# ProPrj_Flipper_-_TweenWave_2025-10-01.net
KiCad netlist of a schematic drawn in EasyEDA Pro
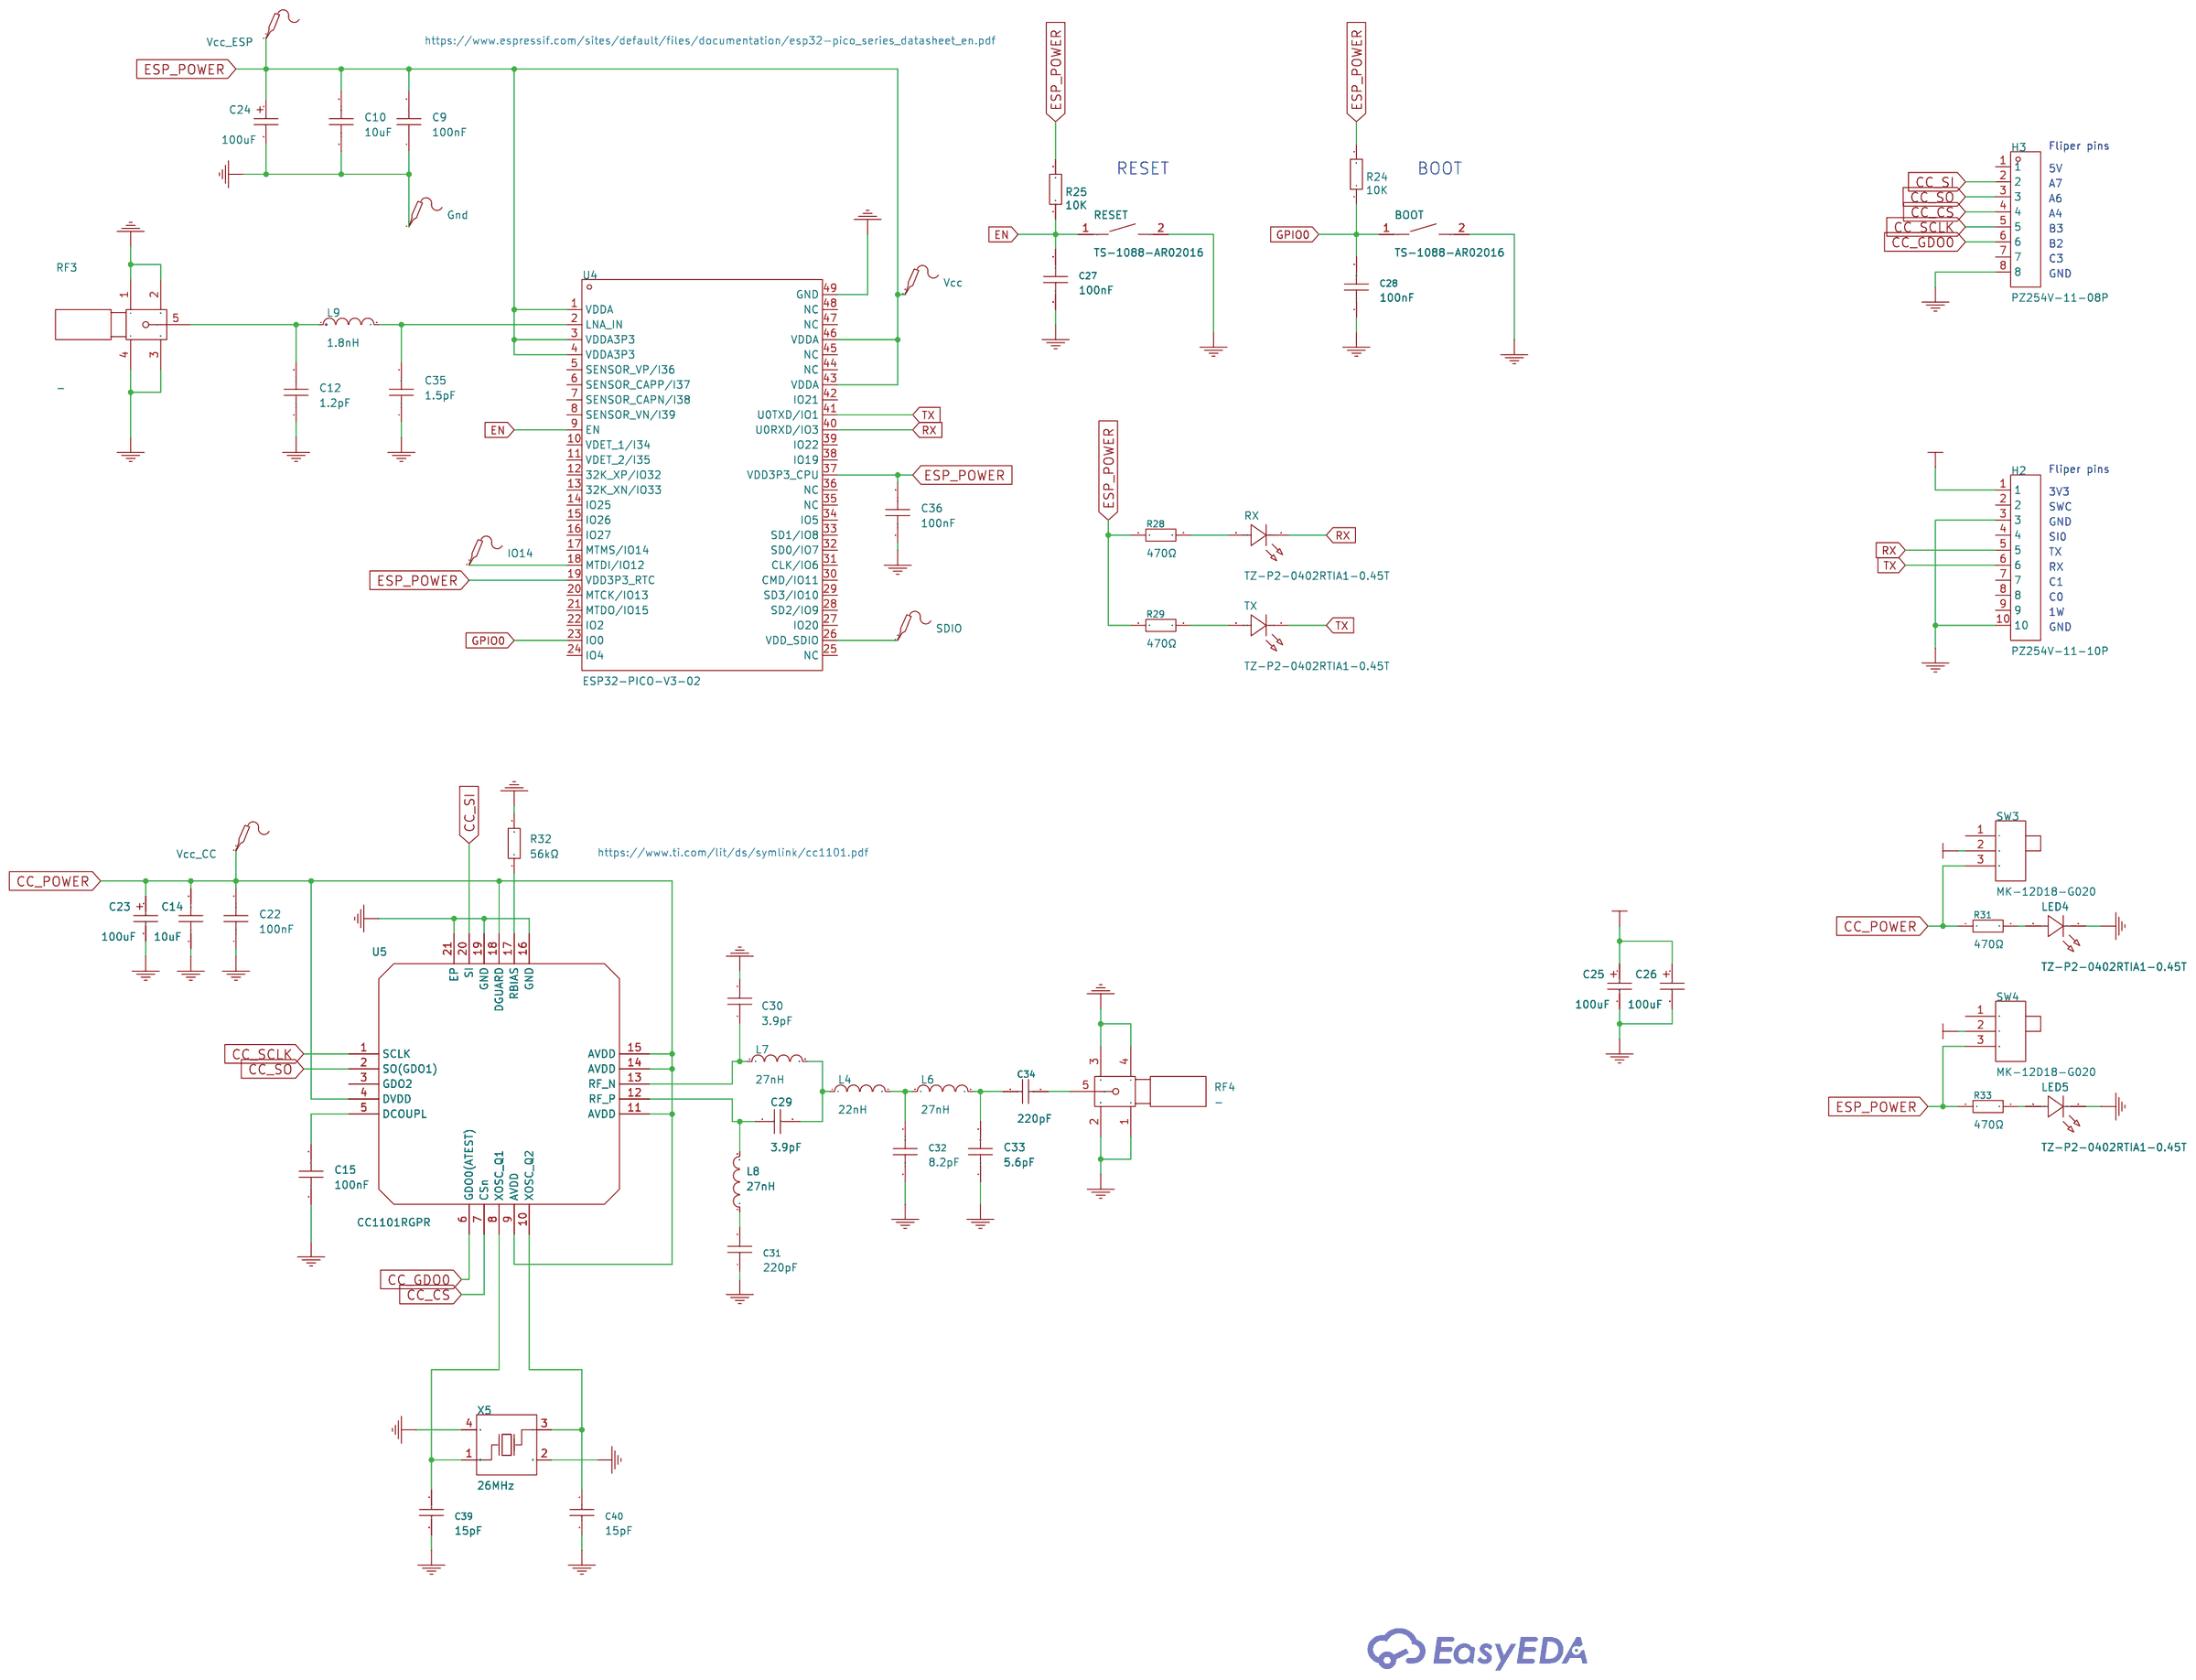
[diagram p0: schematic sheet]

(export (version "E")
  (design (tool "Eeschema 10.0.6"))
  (components
    (comp (ref "BOOT")
      (value "TS-1088-AR02016")
      (footprint "easyedapro:SW-SMD_L3.9-W3.0-P4.45")
      (fields (field (name "Manufacturer") "XUNPU(讯普)"))
      (libsource (lib "easyedapro") (part "TS-1088-AR02016"))
    )
    (comp (ref "C9")
      (value "100nF")
      (footprint "easyedapro:C0603")
      (description "Capacitance:100nF Tolerance:±10% Tolerance:±10% Voltage Rating:50V Temperature Coefficient:X7R")
      (fields
        (field (name "Manufacturer Part") "CC0603KRX7R9BB104")
        (field (name "Manufacturer") "YAGEO(国巨)")
      )
      (libsource (lib "easyedapro") (part "CC0603KRX7R9BB104"))
    )
    (comp (ref "C10")
      (value "10uF")
      (footprint "easyedapro:C0603")
      (fields
        (field (name "Manufacturer Part") "CL10A106MP8NNNC")
        (field (name "Manufacturer") "SAMSUNG(三星)")
      )
      (libsource (lib "easyedapro") (part "CL10A106MP8NNNC"))
    )
    (comp (ref "C12")
      (value "1.2pF")
      (footprint "easyedapro:C0201")
      (fields
        (field (name "Manufacturer Part") "GRM0335C1H1R2BA01D")
        (field (name "Manufacturer") "muRata(村田)")
      )
      (libsource (lib "easyedapro") (part "GRM0335C1H1R2BA01D"))
    )
    (comp (ref "C14")
      (value "10uF")
      (footprint "easyedapro:C0603")
      (fields
        (field (name "Manufacturer Part") "CL10A106MP8NNNC")
        (field (name "Manufacturer") "SAMSUNG(三星)")
      )
      (libsource (lib "easyedapro") (part "CL10A106MP8NNNC"))
    )
    (comp (ref "C15")
      (value "100nF")
      (footprint "easyedapro:C0603")
      (description "Capacitance:100nF Tolerance:±10% Tolerance:±10% Voltage Rating:50V Temperature Coefficient:X7R")
      (fields
        (field (name "Manufacturer Part") "CC0603KRX7R9BB104")
        (field (name "Manufacturer") "YAGEO(国巨)")
      )
      (libsource (lib "easyedapro") (part "CC0603KRX7R9BB104"))
    )
    (comp (ref "C22")
      (value "100nF")
      (footprint "easyedapro:C0603")
      (description "Capacitance:100nF Tolerance:±10% Tolerance:±10% Voltage Rating:50V Temperature Coefficient:X7R")
      (fields
        (field (name "Manufacturer Part") "CC0603KRX7R9BB104")
        (field (name "Manufacturer") "YAGEO(国巨)")
      )
      (libsource (lib "easyedapro") (part "CC0603KRX7R9BB104"))
    )
    (comp (ref "C23")
      (value "100uF")
      (footprint "easyedapro:CASE-B_3528")
      (fields (field (name "Manufacturer Part") "TAJB107K006RNJ") (field (name "Manufacturer") "Kyocera AVX"))
      (libsource (lib "easyedapro") (part "TAJB107K006RNJ"))
    )
    (comp (ref "C24")
      (value "100uF")
      (footprint "easyedapro:CASE-B_3528")
      (fields (field (name "Manufacturer Part") "TAJB107K006RNJ") (field (name "Manufacturer") "Kyocera AVX"))
      (libsource (lib "easyedapro") (part "TAJB107K006RNJ"))
    )
    (comp (ref "C25")
      (value "100uF")
      (footprint "easyedapro:CASE-B_3528")
      (fields (field (name "Manufacturer Part") "TAJB107K006RNJ") (field (name "Manufacturer") "Kyocera AVX"))
      (libsource (lib "easyedapro") (part "TAJB107K006RNJ"))
    )
    (comp (ref "C26")
      (value "100uF")
      (footprint "easyedapro:CASE-B_3528")
      (fields (field (name "Manufacturer Part") "TAJB107K006RNJ") (field (name "Manufacturer") "Kyocera AVX"))
      (libsource (lib "easyedapro") (part "TAJB107K006RNJ"))
    )
    (comp (ref "C27")
      (value "100nF")
      (footprint "easyedapro:C0402")
      (fields
        (field (name "Manufacturer Part") "CC0402KRX7R7BB104")
        (field (name "Manufacturer") "YAGEO(国巨)")
      )
      (libsource (lib "easyedapro") (part "CC0402KRX7R7BB104"))
    )
    (comp (ref "C28")
      (value "100nF")
      (footprint "easyedapro:C0402")
      (fields
        (field (name "Manufacturer Part") "CC0402KRX7R7BB104")
        (field (name "Manufacturer") "YAGEO(国巨)")
      )
      (libsource (lib "easyedapro") (part "CC0402KRX7R7BB104"))
    )
    (comp (ref "C29")
      (value "3.9pF")
      (footprint "easyedapro:C0402")
      (fields (field (name "Manufacturer Part") "0402CG3R9C500NT") (field (name "Manufacturer") "FH(风华)"))
      (libsource (lib "easyedapro") (part "0402CG3R9C500NT"))
    )
    (comp (ref "C30")
      (value "3.9pF")
      (footprint "easyedapro:C0402")
      (fields (field (name "Manufacturer Part") "0402CG3R9C500NT") (field (name "Manufacturer") "FH(风华)"))
      (libsource (lib "easyedapro") (part "0402CG3R9C500NT"))
    )
    (comp (ref "C31")
      (value "220pF")
      (footprint "easyedapro:C0402")
      (description "Capacitance:220pF Tolerance:±5% Tolerance:±5% Voltage Rating:50V Temperature Coefficient:NP0")
      (fields
        (field (name "Manufacturer Part") "CC0402JRNPO9BN221")
        (field (name "Manufacturer") "YAGEO(国巨)")
      )
      (libsource (lib "easyedapro") (part "CC0402JRNPO9BN221"))
    )
    (comp (ref "C32")
      (value "8.2pF")
      (footprint "easyedapro:C0402")
      (fields
        (field (name "Manufacturer Part") "CC0402BRNPO9BN8R2")
        (field (name "Manufacturer") "YAGEO(国巨)")
      )
      (libsource (lib "easyedapro") (part "CC0402BRNPO9BN8R2"))
    )
    (comp (ref "C33")
      (value "5.6pF")
      (footprint "easyedapro:C0402")
      (fields
        (field (name "Manufacturer Part") "CC0402BRNPO9BN5R6")
        (field (name "Manufacturer") "YAGEO(国巨)")
      )
      (libsource (lib "easyedapro") (part "CC0402BRNPO9BN5R6"))
    )
    (comp (ref "C34")
      (value "220pF")
      (footprint "easyedapro:C0402")
      (description "Capacitance:220pF Tolerance:±5% Tolerance:±5% Voltage Rating:50V Temperature Coefficient:NP0")
      (fields
        (field (name "Manufacturer Part") "CC0402JRNPO9BN221")
        (field (name "Manufacturer") "YAGEO(国巨)")
      )
      (libsource (lib "easyedapro") (part "CC0402JRNPO9BN221"))
    )
    (comp (ref "C35")
      (value "1.5pF")
      (footprint "easyedapro:C0201")
      (fields
        (field (name "Manufacturer Part") "GRM0335C1H1R5BA01D")
        (field (name "Manufacturer") "muRata(村田)")
      )
      (libsource (lib "easyedapro") (part "GRM0335C1H1R5BA01D"))
    )
    (comp (ref "C36")
      (value "100nF")
      (footprint "easyedapro:C0603")
      (description "Capacitance:100nF Tolerance:±10% Tolerance:±10% Voltage Rating:50V Temperature Coefficient:X7R")
      (fields
        (field (name "Manufacturer Part") "CC0603KRX7R9BB104")
        (field (name "Manufacturer") "YAGEO(国巨)")
      )
      (libsource (lib "easyedapro") (part "CC0603KRX7R9BB104"))
    )
    (comp (ref "C39")
      (value "15pF")
      (footprint "easyedapro:C0402")
      (fields
        (field (name "Manufacturer Part") "CC0402JRNPO9BN150")
        (field (name "Manufacturer") "YAGEO(国巨)")
      )
      (libsource (lib "easyedapro") (part "CC0402JRNPO9BN150"))
    )
    (comp (ref "C40")
      (value "15pF")
      (footprint "easyedapro:C0402")
      (fields
        (field (name "Manufacturer Part") "CC0402JRNPO9BN150")
        (field (name "Manufacturer") "YAGEO(国巨)")
      )
      (libsource (lib "easyedapro") (part "CC0402JRNPO9BN150"))
    )
    (comp (ref "Gnd")
      (value "~")
      (footprint "easyedapro:Test-Point-0.5mm")
      (description "Test Point 测试点")
      (libsource (lib "easyedapro") (part "Test-Point"))
    )
    (comp (ref "H2")
      (value "PZ254V-11-10P")
      (footprint "easyedapro:HDR-TH_10P-P2.54-V-M")
      (fields (field (name "Manufacturer") "XFCN(兴飞)"))
      (libsource (lib "easyedapro") (part "PZ254V-11-10P"))
    )
    (comp (ref "H3")
      (value "PZ254V-11-08P")
      (footprint "easyedapro:HDR-TH_8P-P2.54-V-M")
      (fields (field (name "Manufacturer") "XFCN(兴飞)"))
      (libsource (lib "easyedapro") (part "PZ254V-11-08P"))
    )
    (comp (ref "IO14")
      (value "~")
      (footprint "easyedapro:Test-Point-0.5mm")
      (description "Test Point 测试点")
      (libsource (lib "easyedapro") (part "Test-Point"))
    )
    (comp (ref "L4")
      (value "22nH")
      (footprint "easyedapro:L0402")
      (fields (field (name "Manufacturer Part") "LQG15HS22NJ02D") (field (name "Manufacturer") "muRata(村田)"))
      (libsource (lib "easyedapro") (part "LQG15HS22NJ02D"))
    )
    (comp (ref "L6")
      (value "27nH")
      (footprint "easyedapro:L0402-RD")
      (fields (field (name "Manufacturer Part") "LQG15HS27NJ02D") (field (name "Manufacturer") "muRata(村田)"))
      (libsource (lib "easyedapro") (part "LQG15HS27NJ02D"))
    )
    (comp (ref "L7")
      (value "27nH")
      (footprint "easyedapro:L0402-RD")
      (fields (field (name "Manufacturer Part") "LQG15HS27NJ02D") (field (name "Manufacturer") "muRata(村田)"))
      (libsource (lib "easyedapro") (part "LQG15HS27NJ02D"))
    )
    (comp (ref "L8")
      (value "27nH")
      (footprint "easyedapro:L0402-RD")
      (fields (field (name "Manufacturer Part") "LQG15HS27NJ02D") (field (name "Manufacturer") "muRata(村田)"))
      (libsource (lib "easyedapro") (part "LQG15HS27NJ02D"))
    )
    (comp (ref "L9")
      (value "1.8nH")
      (footprint "easyedapro:L0201-RD")
      (fields (field (name "Manufacturer Part") "LQP03TN1N8B02D") (field (name "Manufacturer") "muRata(村田)"))
      (libsource (lib "easyedapro") (part "LQP03TN1N8B02D"))
    )
    (comp (ref "LED4")
      (value "TZ-P2-0402RTIA1-0.45T")
      (footprint "easyedapro:LED0402-RD_RED")
      (fields (field (name "Manufacturer") "TUOZHAN(拓展光电)"))
      (libsource (lib "easyedapro") (part "TZ-P2-0402RTIA1-0.45T"))
    )
    (comp (ref "LED5")
      (value "TZ-P2-0402RTIA1-0.45T")
      (footprint "easyedapro:LED0402-RD_RED")
      (fields (field (name "Manufacturer") "TUOZHAN(拓展光电)"))
      (libsource (lib "easyedapro") (part "TZ-P2-0402RTIA1-0.45T"))
    )
    (comp (ref "R24")
      (value "10K")
      (footprint "easyedapro:R0603")
      (fields (field (name "Manufacturer Part") "RC0603DR-0710KL") (field (name "Manufacturer") "YAGEO(国巨)"))
      (libsource (lib "easyedapro") (part "10K"))
    )
    (comp (ref "R25")
      (value "10K")
      (footprint "easyedapro:R0603")
      (fields (field (name "Manufacturer Part") "RC0603DR-0710KL") (field (name "Manufacturer") "YAGEO(国巨)"))
      (libsource (lib "easyedapro") (part "10K"))
    )
    (comp (ref "R28")
      (value "470Ω")
      (footprint "easyedapro:R0402")
      (fields
        (field (name "Manufacturer Part") "0402WGF4700TCE")
        (field (name "Manufacturer") "UNI-ROYAL(厚声)")
      )
      (libsource (lib "easyedapro") (part "0402WGF4700TCE"))
    )
    (comp (ref "R29")
      (value "470Ω")
      (footprint "easyedapro:R0402")
      (fields
        (field (name "Manufacturer Part") "0402WGF4700TCE")
        (field (name "Manufacturer") "UNI-ROYAL(厚声)")
      )
      (libsource (lib "easyedapro") (part "0402WGF4700TCE"))
    )
    (comp (ref "R31")
      (value "470Ω")
      (footprint "easyedapro:R0402")
      (fields
        (field (name "Manufacturer Part") "0402WGF4700TCE")
        (field (name "Manufacturer") "UNI-ROYAL(厚声)")
      )
      (libsource (lib "easyedapro") (part "0402WGF4700TCE"))
    )
    (comp (ref "R32")
      (value "56kΩ")
      (footprint "easyedapro:R0402")
      (fields
        (field (name "Manufacturer Part") "0402WGF5602TCE")
        (field (name "Manufacturer") "UNI-ROYAL(厚声)")
      )
      (libsource (lib "easyedapro") (part "0402WGF5602TCE"))
    )
    (comp (ref "R33")
      (value "470Ω")
      (footprint "easyedapro:R0402")
      (fields
        (field (name "Manufacturer Part") "0402WGF4700TCE")
        (field (name "Manufacturer") "UNI-ROYAL(厚声)")
      )
      (libsource (lib "easyedapro") (part "0402WGF4700TCE"))
    )
    (comp (ref "RESET")
      (value "TS-1088-AR02016")
      (footprint "easyedapro:SW-SMD_L3.9-W3.0-P4.45")
      (fields (field (name "Manufacturer") "XUNPU(讯普)"))
      (libsource (lib "easyedapro") (part "TS-1088-AR02016"))
    )
    (comp (ref "RF3")
      (value "-")
      (footprint "easyedapro:SMA-SMD_BWSMA-KE-P001")
      (fields
        (field (name "Manufacturer Part") "BWSMA-KE-P001")
        (field (name "Manufacturer") "BAT WIRELESS(蝙蝠无线)")
      )
      (libsource (lib "easyedapro") (part "BWSMA-KE-P001"))
    )
    (comp (ref "RF4")
      (value "-")
      (footprint "easyedapro:SMA-SMD_BWSMA-KE-P001")
      (fields
        (field (name "Manufacturer Part") "BWSMA-KE-P001")
        (field (name "Manufacturer") "BAT WIRELESS(蝙蝠无线)")
      )
      (libsource (lib "easyedapro") (part "BWSMA-KE-P001"))
    )
    (comp (ref "RX")
      (value "TZ-P2-0402RTIA1-0.45T")
      (footprint "easyedapro:LED0402-RD_RED")
      (fields (field (name "Manufacturer") "TUOZHAN(拓展光电)"))
      (libsource (lib "easyedapro") (part "TZ-P2-0402RTIA1-0.45T"))
    )
    (comp (ref "SDIO")
      (value "~")
      (footprint "easyedapro:Test-Point-0.5mm")
      (description "Test Point 测试点")
      (libsource (lib "easyedapro") (part "Test-Point"))
    )
    (comp (ref "SW3")
      (value "MK-12D18-G020")
      (footprint "easyedapro:SW-TH_MK-12D18-G040")
      (fields (field (name "Manufacturer") "G-Switch(品赞)"))
      (libsource (lib "easyedapro") (part "MK-12D18-G020"))
    )
    (comp (ref "SW4")
      (value "MK-12D18-G020")
      (footprint "easyedapro:SW-TH_MK-12D18-G040")
      (fields (field (name "Manufacturer") "G-Switch(品赞)"))
      (libsource (lib "easyedapro") (part "MK-12D18-G020"))
    )
    (comp (ref "TX")
      (value "TZ-P2-0402RTIA1-0.45T")
      (footprint "easyedapro:LED0402-RD_RED")
      (fields (field (name "Manufacturer") "TUOZHAN(拓展光电)"))
      (libsource (lib "easyedapro") (part "TZ-P2-0402RTIA1-0.45T"))
    )
    (comp (ref "U4")
      (value "ESP32-PICO-V3-02")
      (footprint "easyedapro:QFN-48_L7.0-W7.0-P0.50-BL-EP5.1")
      (fields (field (name "Manufacturer") "ESPRESSIF(乐鑫)"))
      (libsource (lib "easyedapro") (part "ESP32-PICO-V3-02"))
    )
    (comp (ref "U5")
      (value "CC1101RGPR")
      (footprint "easyedapro:QFN-20_L4.0-W4.0-P0.5-TL-EP")
      (fields (field (name "Manufacturer") "TI(德州仪器)"))
      (libsource (lib "easyedapro") (part "CC1101RGPR"))
    )
    (comp (ref "Vcc")
      (value "~")
      (footprint "easyedapro:Test-Point-0.5mm")
      (description "Test Point 测试点")
      (libsource (lib "easyedapro") (part "Test-Point"))
    )
    (comp (ref "Vcc_CC")
      (value "~")
      (footprint "easyedapro:Test-Point-0.5mm")
      (description "Test Point 测试点")
      (libsource (lib "easyedapro") (part "Test-Point"))
    )
    (comp (ref "Vcc_ESP")
      (value "~")
      (footprint "easyedapro:Test-Point-0.5mm")
      (description "Test Point 测试点")
      (libsource (lib "easyedapro") (part "Test-Point"))
    )
    (comp (ref "X5")
      (value "26MHz")
      (footprint "easyedapro:CRYSTAL-SMD_4P-L3.2-W2.5-BL")
      (fields (field (name "Manufacturer Part") "X322526MMB4SI") (field (name "Manufacturer") "YXC(扬兴晶振)"))
      (libsource (lib "easyedapro") (part "X322526MMB4SI"))
    )
  )
  (nets
    (net (code "1") (name "3V3") (class "Default")
      (node (ref "C25") (pin "1") (pinfunction "1_1") (pintype "input"))
      (node (ref "C26") (pin "1") (pinfunction "1_1") (pintype "input"))
      (node (ref "H2") (pin "1") (pinfunction "1_1") (pintype "unspecified"))
      (node (ref "SW3") (pin "2") (pinfunction "2_2") (pintype "unspecified"))
      (node (ref "SW4") (pin "2") (pinfunction "2_2") (pintype "unspecified"))
    )
    (net (code "2") (name "CC_CS") (class "Default")
      (node (ref "H3") (pin "4") (pinfunction "4_4") (pintype "unspecified"))
      (node (ref "U5") (pin "7") (pinfunction "CSn_7") (pintype "unspecified"))
    )
    (net (code "3") (name "CC_GDO0") (class "Default")
      (node (ref "H3") (pin "6") (pinfunction "6_6") (pintype "unspecified"))
      (node (ref "U5") (pin "6") (pinfunction "GDO0(ATEST)_6") (pintype "unspecified"))
    )
    (net (code "4") (name "CC_POWER") (class "Default")
      (node (ref "C14") (pin "2") (pinfunction "2_2") (pintype "unspecified"))
      (node (ref "C22") (pin "2") (pinfunction "2_2") (pintype "unspecified"))
      (node (ref "C23") (pin "1") (pinfunction "1_1") (pintype "input"))
      (node (ref "R31") (pin "1") (pinfunction "1_1") (pintype "input"))
      (node (ref "SW3") (pin "3") (pinfunction "3_3") (pintype "unspecified"))
      (node (ref "U5") (pin "11") (pinfunction "AVDD_11") (pintype "unspecified"))
      (node (ref "U5") (pin "14") (pinfunction "AVDD_14") (pintype "unspecified"))
      (node (ref "U5") (pin "15") (pinfunction "AVDD_15") (pintype "unspecified"))
      (node (ref "U5") (pin "18") (pinfunction "DGUARD_18") (pintype "unspecified"))
      (node (ref "U5") (pin "4") (pinfunction "DVDD_4") (pintype "unspecified"))
      (node (ref "U5") (pin "9") (pinfunction "AVDD_9") (pintype "unspecified"))
      (node (ref "Vcc_CC") (pin "1") (pinfunction "1_1") (pintype "unspecified"))
    )
    (net (code "5") (name "CC_SCLK") (class "Default")
      (node (ref "H3") (pin "5") (pinfunction "5_5") (pintype "unspecified"))
      (node (ref "U5") (pin "1") (pinfunction "SCLK_1") (pintype "unspecified"))
    )
    (net (code "6") (name "CC_SI") (class "Default")
      (node (ref "H3") (pin "2") (pinfunction "2_2") (pintype "unspecified"))
      (node (ref "U5") (pin "20") (pinfunction "SI_20") (pintype "unspecified"))
    )
    (net (code "7") (name "CC_SO") (class "Default")
      (node (ref "H3") (pin "3") (pinfunction "3_3") (pintype "unspecified"))
      (node (ref "U5") (pin "2") (pinfunction "SO(GDO1)_2") (pintype "unspecified"))
    )
    (net (code "8") (name "EN") (class "Default")
      (node (ref "C27") (pin "2") (pinfunction "2_2") (pintype "input"))
      (node (ref "R25") (pin "1") (pinfunction "1_1") (pintype "input"))
      (node (ref "RESET") (pin "1") (pinfunction "1_1") (pintype "unspecified"))
      (node (ref "U4") (pin "9") (pinfunction "EN_9") (pintype "unspecified"))
    )
    (net (code "9") (name "ESP_POWER") (class "Default")
      (node (ref "C10") (pin "2") (pinfunction "2_2") (pintype "unspecified"))
      (node (ref "C24") (pin "1") (pinfunction "1_1") (pintype "input"))
      (node (ref "C36") (pin "2") (pinfunction "2_2") (pintype "unspecified"))
      (node (ref "C9") (pin "2") (pinfunction "2_2") (pintype "unspecified"))
      (node (ref "R24") (pin "2") (pinfunction "2_2") (pintype "input"))
      (node (ref "R25") (pin "2") (pinfunction "2_2") (pintype "input"))
      (node (ref "R28") (pin "1") (pinfunction "1_1") (pintype "input"))
      (node (ref "R29") (pin "1") (pinfunction "1_1") (pintype "input"))
      (node (ref "R33") (pin "1") (pinfunction "1_1") (pintype "input"))
      (node (ref "SW4") (pin "3") (pinfunction "3_3") (pintype "unspecified"))
      (node (ref "U4") (pin "1") (pinfunction "VDDA_1") (pintype "unspecified"))
      (node (ref "U4") (pin "19") (pinfunction "VDD3P3_RTC_19") (pintype "unspecified"))
      (node (ref "U4") (pin "3") (pinfunction "VDDA3P3_3") (pintype "unspecified"))
      (node (ref "U4") (pin "37") (pinfunction "VDD3P3_CPU_37") (pintype "unspecified"))
      (node (ref "U4") (pin "4") (pinfunction "VDDA3P3_4") (pintype "unspecified"))
      (node (ref "U4") (pin "43") (pinfunction "VDDA_43") (pintype "unspecified"))
      (node (ref "U4") (pin "46") (pinfunction "VDDA_46") (pintype "unspecified"))
      (node (ref "Vcc") (pin "1") (pinfunction "1_1") (pintype "unspecified"))
      (node (ref "Vcc_ESP") (pin "1") (pinfunction "1_1") (pintype "unspecified"))
    )
    (net (code "10") (name "GND") (class "Default")
      (node (ref "BOOT") (pin "2") (pinfunction "2_2") (pintype "unspecified"))
      (node (ref "C10") (pin "1") (pinfunction "1_1") (pintype "unspecified"))
      (node (ref "C12") (pin "1") (pinfunction "1_1") (pintype "unspecified"))
      (node (ref "C14") (pin "1") (pinfunction "1_1") (pintype "unspecified"))
      (node (ref "C15") (pin "1") (pinfunction "1_1") (pintype "unspecified"))
      (node (ref "C22") (pin "1") (pinfunction "1_1") (pintype "unspecified"))
      (node (ref "C23") (pin "2") (pinfunction "2_2") (pintype "input"))
      (node (ref "C24") (pin "2") (pinfunction "2_2") (pintype "input"))
      (node (ref "C25") (pin "2") (pinfunction "2_2") (pintype "input"))
      (node (ref "C26") (pin "2") (pinfunction "2_2") (pintype "input"))
      (node (ref "C27") (pin "1") (pinfunction "1_1") (pintype "input"))
      (node (ref "C28") (pin "1") (pinfunction "1_1") (pintype "input"))
      (node (ref "C30") (pin "2") (pinfunction "2_2") (pintype "input"))
      (node (ref "C31") (pin "1") (pinfunction "1_1") (pintype "input"))
      (node (ref "C32") (pin "2") (pinfunction "2_2") (pintype "input"))
      (node (ref "C33") (pin "1") (pinfunction "1_1") (pintype "unspecified"))
      (node (ref "C35") (pin "1") (pinfunction "1_1") (pintype "unspecified"))
      (node (ref "C36") (pin "1") (pinfunction "1_1") (pintype "unspecified"))
      (node (ref "C39") (pin "1") (pinfunction "1_1") (pintype "input"))
      (node (ref "C40") (pin "1") (pinfunction "1_1") (pintype "input"))
      (node (ref "C9") (pin "1") (pinfunction "1_1") (pintype "unspecified"))
      (node (ref "Gnd") (pin "1") (pinfunction "1_1") (pintype "unspecified"))
      (node (ref "H2") (pin "10") (pinfunction "10_10") (pintype "unspecified"))
      (node (ref "H2") (pin "3") (pinfunction "3_3") (pintype "unspecified"))
      (node (ref "H3") (pin "8") (pinfunction "8_8") (pintype "unspecified"))
      (node (ref "LED4") (pin "1") (pinfunction "K_1") (pintype "unspecified"))
      (node (ref "LED5") (pin "1") (pinfunction "K_1") (pintype "unspecified"))
      (node (ref "R32") (pin "2") (pinfunction "2_2") (pintype "input"))
      (node (ref "RESET") (pin "2") (pinfunction "2_2") (pintype "unspecified"))
      (node (ref "RF3") (pin "1") (pinfunction "1_1") (pintype "unspecified"))
      (node (ref "RF3") (pin "2") (pinfunction "2_2") (pintype "unspecified"))
      (node (ref "RF3") (pin "3") (pinfunction "3_3") (pintype "unspecified"))
      (node (ref "RF3") (pin "4") (pinfunction "4_4") (pintype "unspecified"))
      (node (ref "RF4") (pin "1") (pinfunction "1_1") (pintype "unspecified"))
      (node (ref "RF4") (pin "2") (pinfunction "2_2") (pintype "unspecified"))
      (node (ref "RF4") (pin "3") (pinfunction "3_3") (pintype "unspecified"))
      (node (ref "RF4") (pin "4") (pinfunction "4_4") (pintype "unspecified"))
      (node (ref "U4") (pin "49") (pinfunction "GND_49") (pintype "unspecified"))
      (node (ref "U5") (pin "16") (pinfunction "GND_16") (pintype "unspecified"))
      (node (ref "U5") (pin "19") (pinfunction "GND_19") (pintype "unspecified"))
      (node (ref "U5") (pin "21") (pinfunction "EP_21") (pintype "unspecified"))
      (node (ref "X5") (pin "2") (pinfunction "GND_2") (pintype "unspecified"))
      (node (ref "X5") (pin "4") (pinfunction "GND_4") (pintype "unspecified"))
    )
    (net (code "11") (name "GPIO0") (class "Default")
      (node (ref "BOOT") (pin "1") (pinfunction "1_1") (pintype "unspecified"))
      (node (ref "C28") (pin "2") (pinfunction "2_2") (pintype "input"))
      (node (ref "R24") (pin "1") (pinfunction "1_1") (pintype "input"))
      (node (ref "U4") (pin "23") (pinfunction "IO0_23") (pintype "unspecified"))
    )
    (net (code "12") (name "Net-(C12-Pad2)") (class "Default")
      (node (ref "C12") (pin "2") (pinfunction "2_2") (pintype "unspecified"))
      (node (ref "L9") (pin "1") (pinfunction "1_1") (pintype "input"))
      (node (ref "RF3") (pin "5") (pinfunction "5_5") (pintype "unspecified"))
    )
    (net (code "13") (name "Net-(C29-Pad2)") (class "Default")
      (node (ref "C29") (pin "2") (pinfunction "2_2") (pintype "input"))
      (node (ref "L4") (pin "1") (pinfunction "1_1") (pintype "unspecified"))
      (node (ref "L7") (pin "2") (pinfunction "2_2") (pintype "unspecified"))
    )
    (net (code "14") (name "Net-(C31-Pad2)") (class "Default")
      (node (ref "C31") (pin "2") (pinfunction "2_2") (pintype "input"))
      (node (ref "L8") (pin "1") (pinfunction "1_1") (pintype "unspecified"))
    )
    (net (code "15") (name "Net-(C32-Pad1)") (class "Default")
      (node (ref "C32") (pin "1") (pinfunction "1_1") (pintype "input"))
      (node (ref "L4") (pin "2") (pinfunction "2_2") (pintype "unspecified"))
      (node (ref "L6") (pin "1") (pinfunction "1_1") (pintype "unspecified"))
    )
    (net (code "16") (name "Net-(C33-Pad2)") (class "Default")
      (node (ref "C33") (pin "2") (pinfunction "2_2") (pintype "unspecified"))
      (node (ref "C34") (pin "2") (pinfunction "2_2") (pintype "input"))
      (node (ref "L6") (pin "2") (pinfunction "2_2") (pintype "unspecified"))
    )
    (net (code "17") (name "Net-(C34-Pad1)") (class "Default")
      (node (ref "C34") (pin "1") (pinfunction "1_1") (pintype "input"))
      (node (ref "RF4") (pin "5") (pinfunction "5_5") (pintype "unspecified"))
    )
    (net (code "18") (name "Net-(LED4-A)") (class "Default")
      (node (ref "LED4") (pin "2") (pinfunction "A_2") (pintype "unspecified"))
      (node (ref "R31") (pin "2") (pinfunction "2_2") (pintype "input"))
    )
    (net (code "19") (name "Net-(LED5-A)") (class "Default")
      (node (ref "LED5") (pin "2") (pinfunction "A_2") (pintype "unspecified"))
      (node (ref "R33") (pin "2") (pinfunction "2_2") (pintype "input"))
    )
    (net (code "20") (name "Net-(RX-A)") (class "Default")
      (node (ref "R28") (pin "2") (pinfunction "2_2") (pintype "input"))
      (node (ref "RX") (pin "2") (pinfunction "A_2") (pintype "unspecified"))
    )
    (net (code "21") (name "Net-(TX-A)") (class "Default")
      (node (ref "R29") (pin "2") (pinfunction "2_2") (pintype "input"))
      (node (ref "TX") (pin "2") (pinfunction "A_2") (pintype "unspecified"))
    )
    (net (code "22") (name "Net-(U4-LNA_IN)") (class "Default")
      (node (ref "C35") (pin "2") (pinfunction "2_2") (pintype "unspecified"))
      (node (ref "L9") (pin "2") (pinfunction "2_2") (pintype "input"))
      (node (ref "U4") (pin "2") (pinfunction "LNA_IN_2") (pintype "unspecified"))
    )
    (net (code "23") (name "Net-(U4-MTDI{slash}IO12)") (class "Default")
      (node (ref "IO14") (pin "1") (pinfunction "1_1") (pintype "unspecified"))
      (node (ref "U4") (pin "18") (pinfunction "MTDI/IO12_18") (pintype "unspecified"))
    )
    (net (code "24") (name "Net-(U4-VDD_SDIO)") (class "Default")
      (node (ref "SDIO") (pin "1") (pinfunction "1_1") (pintype "unspecified"))
      (node (ref "U4") (pin "26") (pinfunction "VDD_SDIO_26") (pintype "unspecified"))
    )
    (net (code "25") (name "Net-(U5-DCOUPL)") (class "Default")
      (node (ref "C15") (pin "2") (pinfunction "2_2") (pintype "unspecified"))
      (node (ref "U5") (pin "5") (pinfunction "DCOUPL_5") (pintype "unspecified"))
    )
    (net (code "26") (name "Net-(U5-RBIAS)") (class "Default")
      (node (ref "R32") (pin "1") (pinfunction "1_1") (pintype "input"))
      (node (ref "U5") (pin "17") (pinfunction "RBIAS_17") (pintype "unspecified"))
    )
    (net (code "27") (name "Net-(U5-RF_N)") (class "Default")
      (node (ref "C30") (pin "1") (pinfunction "1_1") (pintype "input"))
      (node (ref "L7") (pin "1") (pinfunction "1_1") (pintype "unspecified"))
      (node (ref "U5") (pin "13") (pinfunction "RF_N_13") (pintype "unspecified"))
    )
    (net (code "28") (name "Net-(U5-RF_P)") (class "Default")
      (node (ref "C29") (pin "1") (pinfunction "1_1") (pintype "input"))
      (node (ref "L8") (pin "2") (pinfunction "2_2") (pintype "unspecified"))
      (node (ref "U5") (pin "12") (pinfunction "RF_P_12") (pintype "unspecified"))
    )
    (net (code "29") (name "Net-(U5-XOSC_Q1)") (class "Default")
      (node (ref "C39") (pin "2") (pinfunction "2_2") (pintype "input"))
      (node (ref "U5") (pin "8") (pinfunction "XOSC_Q1_8") (pintype "unspecified"))
      (node (ref "X5") (pin "1") (pinfunction "OSC1_1") (pintype "unspecified"))
    )
    (net (code "30") (name "Net-(U5-XOSC_Q2)") (class "Default")
      (node (ref "C40") (pin "2") (pinfunction "2_2") (pintype "input"))
      (node (ref "U5") (pin "10") (pinfunction "XOSC_Q2_10") (pintype "unspecified"))
      (node (ref "X5") (pin "3") (pinfunction "OSC2_3") (pintype "unspecified"))
    )
    (net (code "31") (name "RX") (class "Default")
      (node (ref "H2") (pin "5") (pinfunction "5_5") (pintype "unspecified"))
      (node (ref "RX") (pin "1") (pinfunction "K_1") (pintype "unspecified"))
      (node (ref "U4") (pin "40") (pinfunction "U0RXD/IO3_40") (pintype "unspecified"))
    )
    (net (code "32") (name "TX") (class "Default")
      (node (ref "H2") (pin "6") (pinfunction "6_6") (pintype "unspecified"))
      (node (ref "TX") (pin "1") (pinfunction "K_1") (pintype "unspecified"))
      (node (ref "U4") (pin "41") (pinfunction "U0TXD/IO1_41") (pintype "unspecified"))
    )
    (net (code "33") (name "unconnected-(H2-Pad2)") (class "Default")
      (node (ref "H2") (pin "2") (pinfunction "2_2") (pintype "unspecified"))
    )
    (net (code "34") (name "unconnected-(H2-Pad4)") (class "Default")
      (node (ref "H2") (pin "4") (pinfunction "4_4") (pintype "unspecified"))
    )
    (net (code "35") (name "unconnected-(H2-Pad7)") (class "Default")
      (node (ref "H2") (pin "7") (pinfunction "7_7") (pintype "unspecified"))
    )
    (net (code "36") (name "unconnected-(H2-Pad8)") (class "Default")
      (node (ref "H2") (pin "8") (pinfunction "8_8") (pintype "unspecified"))
    )
    (net (code "37") (name "unconnected-(H2-Pad9)") (class "Default")
      (node (ref "H2") (pin "9") (pinfunction "9_9") (pintype "unspecified"))
    )
    (net (code "38") (name "unconnected-(H3-Pad1)") (class "Default")
      (node (ref "H3") (pin "1") (pinfunction "1_1") (pintype "unspecified"))
    )
    (net (code "39") (name "unconnected-(H3-Pad7)") (class "Default")
      (node (ref "H3") (pin "7") (pinfunction "7_7") (pintype "unspecified"))
    )
    (net (code "40") (name "unconnected-(SW3-Pad1)") (class "Default")
      (node (ref "SW3") (pin "1") (pinfunction "1_1") (pintype "unspecified"))
    )
    (net (code "41") (name "unconnected-(SW4-Pad1)") (class "Default")
      (node (ref "SW4") (pin "1") (pinfunction "1_1") (pintype "unspecified"))
    )
    (net (code "42") (name "unconnected-(U4-32K_XN{slash}IO33-Pad13)") (class "Default")
      (node (ref "U4") (pin "13") (pinfunction "32K_XN/IO33_13") (pintype "unspecified"))
    )
    (net (code "43") (name "unconnected-(U4-32K_XP{slash}IO32-Pad12)") (class "Default")
      (node (ref "U4") (pin "12") (pinfunction "32K_XP/IO32_12") (pintype "unspecified"))
    )
    (net (code "44") (name "unconnected-(U4-CLK{slash}IO6-Pad31)") (class "Default")
      (node (ref "U4") (pin "31") (pinfunction "CLK/IO6_31") (pintype "unspecified"))
    )
    (net (code "45") (name "unconnected-(U4-CMD{slash}IO11-Pad30)") (class "Default")
      (node (ref "U4") (pin "30") (pinfunction "CMD/IO11_30") (pintype "unspecified"))
    )
    (net (code "46") (name "unconnected-(U4-IO2-Pad22)") (class "Default")
      (node (ref "U4") (pin "22") (pinfunction "IO2_22") (pintype "unspecified"))
    )
    (net (code "47") (name "unconnected-(U4-IO4-Pad24)") (class "Default")
      (node (ref "U4") (pin "24") (pinfunction "IO4_24") (pintype "unspecified"))
    )
    (net (code "48") (name "unconnected-(U4-IO5-Pad34)") (class "Default")
      (node (ref "U4") (pin "34") (pinfunction "IO5_34") (pintype "unspecified"))
    )
    (net (code "49") (name "unconnected-(U4-IO19-Pad38)") (class "Default")
      (node (ref "U4") (pin "38") (pinfunction "IO19_38") (pintype "unspecified"))
    )
    (net (code "50") (name "unconnected-(U4-IO20-Pad27)") (class "Default")
      (node (ref "U4") (pin "27") (pinfunction "IO20_27") (pintype "unspecified"))
    )
    (net (code "51") (name "unconnected-(U4-IO21-Pad42)") (class "Default")
      (node (ref "U4") (pin "42") (pinfunction "IO21_42") (pintype "unspecified"))
    )
    (net (code "52") (name "unconnected-(U4-IO22-Pad39)") (class "Default")
      (node (ref "U4") (pin "39") (pinfunction "IO22_39") (pintype "unspecified"))
    )
    (net (code "53") (name "unconnected-(U4-IO25-Pad14)") (class "Default")
      (node (ref "U4") (pin "14") (pinfunction "IO25_14") (pintype "unspecified"))
    )
    (net (code "54") (name "unconnected-(U4-IO26-Pad15)") (class "Default")
      (node (ref "U4") (pin "15") (pinfunction "IO26_15") (pintype "unspecified"))
    )
    (net (code "55") (name "unconnected-(U4-IO27-Pad16)") (class "Default")
      (node (ref "U4") (pin "16") (pinfunction "IO27_16") (pintype "unspecified"))
    )
    (net (code "56") (name "unconnected-(U4-MTCK{slash}IO13-Pad20)") (class "Default")
      (node (ref "U4") (pin "20") (pinfunction "MTCK/IO13_20") (pintype "unspecified"))
    )
    (net (code "57") (name "unconnected-(U4-MTDO{slash}IO15-Pad21)") (class "Default")
      (node (ref "U4") (pin "21") (pinfunction "MTDO/IO15_21") (pintype "unspecified"))
    )
    (net (code "58") (name "unconnected-(U4-MTMS{slash}IO14-Pad17)") (class "Default")
      (node (ref "U4") (pin "17") (pinfunction "MTMS/IO14_17") (pintype "unspecified"))
    )
    (net (code "59") (name "unconnected-(U4-NC-Pad25)") (class "Default")
      (node (ref "U4") (pin "25") (pinfunction "NC_25") (pintype "unspecified"))
    )
    (net (code "60") (name "unconnected-(U4-NC-Pad35)") (class "Default")
      (node (ref "U4") (pin "35") (pinfunction "NC_35") (pintype "unspecified"))
    )
    (net (code "61") (name "unconnected-(U4-NC-Pad36)") (class "Default")
      (node (ref "U4") (pin "36") (pinfunction "NC_36") (pintype "unspecified"))
    )
    (net (code "62") (name "unconnected-(U4-NC-Pad44)") (class "Default")
      (node (ref "U4") (pin "44") (pinfunction "NC_44") (pintype "unspecified"))
    )
    (net (code "63") (name "unconnected-(U4-NC-Pad45)") (class "Default")
      (node (ref "U4") (pin "45") (pinfunction "NC_45") (pintype "unspecified"))
    )
    (net (code "64") (name "unconnected-(U4-NC-Pad47)") (class "Default")
      (node (ref "U4") (pin "47") (pinfunction "NC_47") (pintype "unspecified"))
    )
    (net (code "65") (name "unconnected-(U4-NC-Pad48)") (class "Default")
      (node (ref "U4") (pin "48") (pinfunction "NC_48") (pintype "unspecified"))
    )
    (net (code "66") (name "unconnected-(U4-SD0{slash}IO7-Pad32)") (class "Default")
      (node (ref "U4") (pin "32") (pinfunction "SD0/IO7_32") (pintype "unspecified"))
    )
    (net (code "67") (name "unconnected-(U4-SD1{slash}IO8-Pad33)") (class "Default")
      (node (ref "U4") (pin "33") (pinfunction "SD1/IO8_33") (pintype "unspecified"))
    )
    (net (code "68") (name "unconnected-(U4-SD2{slash}IO9-Pad28)") (class "Default")
      (node (ref "U4") (pin "28") (pinfunction "SD2/IO9_28") (pintype "unspecified"))
    )
    (net (code "69") (name "unconnected-(U4-SD3{slash}IO10-Pad29)") (class "Default")
      (node (ref "U4") (pin "29") (pinfunction "SD3/IO10_29") (pintype "unspecified"))
    )
    (net (code "70") (name "unconnected-(U4-SENSOR_CAPN{slash}I38-Pad7)") (class "Default")
      (node (ref "U4") (pin "7") (pinfunction "SENSOR_CAPN/I38_7") (pintype "unspecified"))
    )
    (net (code "71") (name "unconnected-(U4-SENSOR_CAPP{slash}I37-Pad6)") (class "Default")
      (node (ref "U4") (pin "6") (pinfunction "SENSOR_CAPP/I37_6") (pintype "unspecified"))
    )
    (net (code "72") (name "unconnected-(U4-SENSOR_VN{slash}I39-Pad8)") (class "Default")
      (node (ref "U4") (pin "8") (pinfunction "SENSOR_VN/I39_8") (pintype "unspecified"))
    )
    (net (code "73") (name "unconnected-(U4-SENSOR_VP{slash}I36-Pad5)") (class "Default")
      (node (ref "U4") (pin "5") (pinfunction "SENSOR_VP/I36_5") (pintype "unspecified"))
    )
    (net (code "74") (name "unconnected-(U4-VDET_1{slash}I34-Pad10)") (class "Default")
      (node (ref "U4") (pin "10") (pinfunction "VDET_1/I34_10") (pintype "unspecified"))
    )
    (net (code "75") (name "unconnected-(U4-VDET_2{slash}I35-Pad11)") (class "Default")
      (node (ref "U4") (pin "11") (pinfunction "VDET_2/I35_11") (pintype "unspecified"))
    )
    (net (code "76") (name "unconnected-(U5-GDO2-Pad3)") (class "Default")
      (node (ref "U5") (pin "3") (pinfunction "GDO2_3") (pintype "unspecified"))
    )
  )
)
